# PRG_1_0.net
KiCad netlist of a schematic drawn in EAGLE
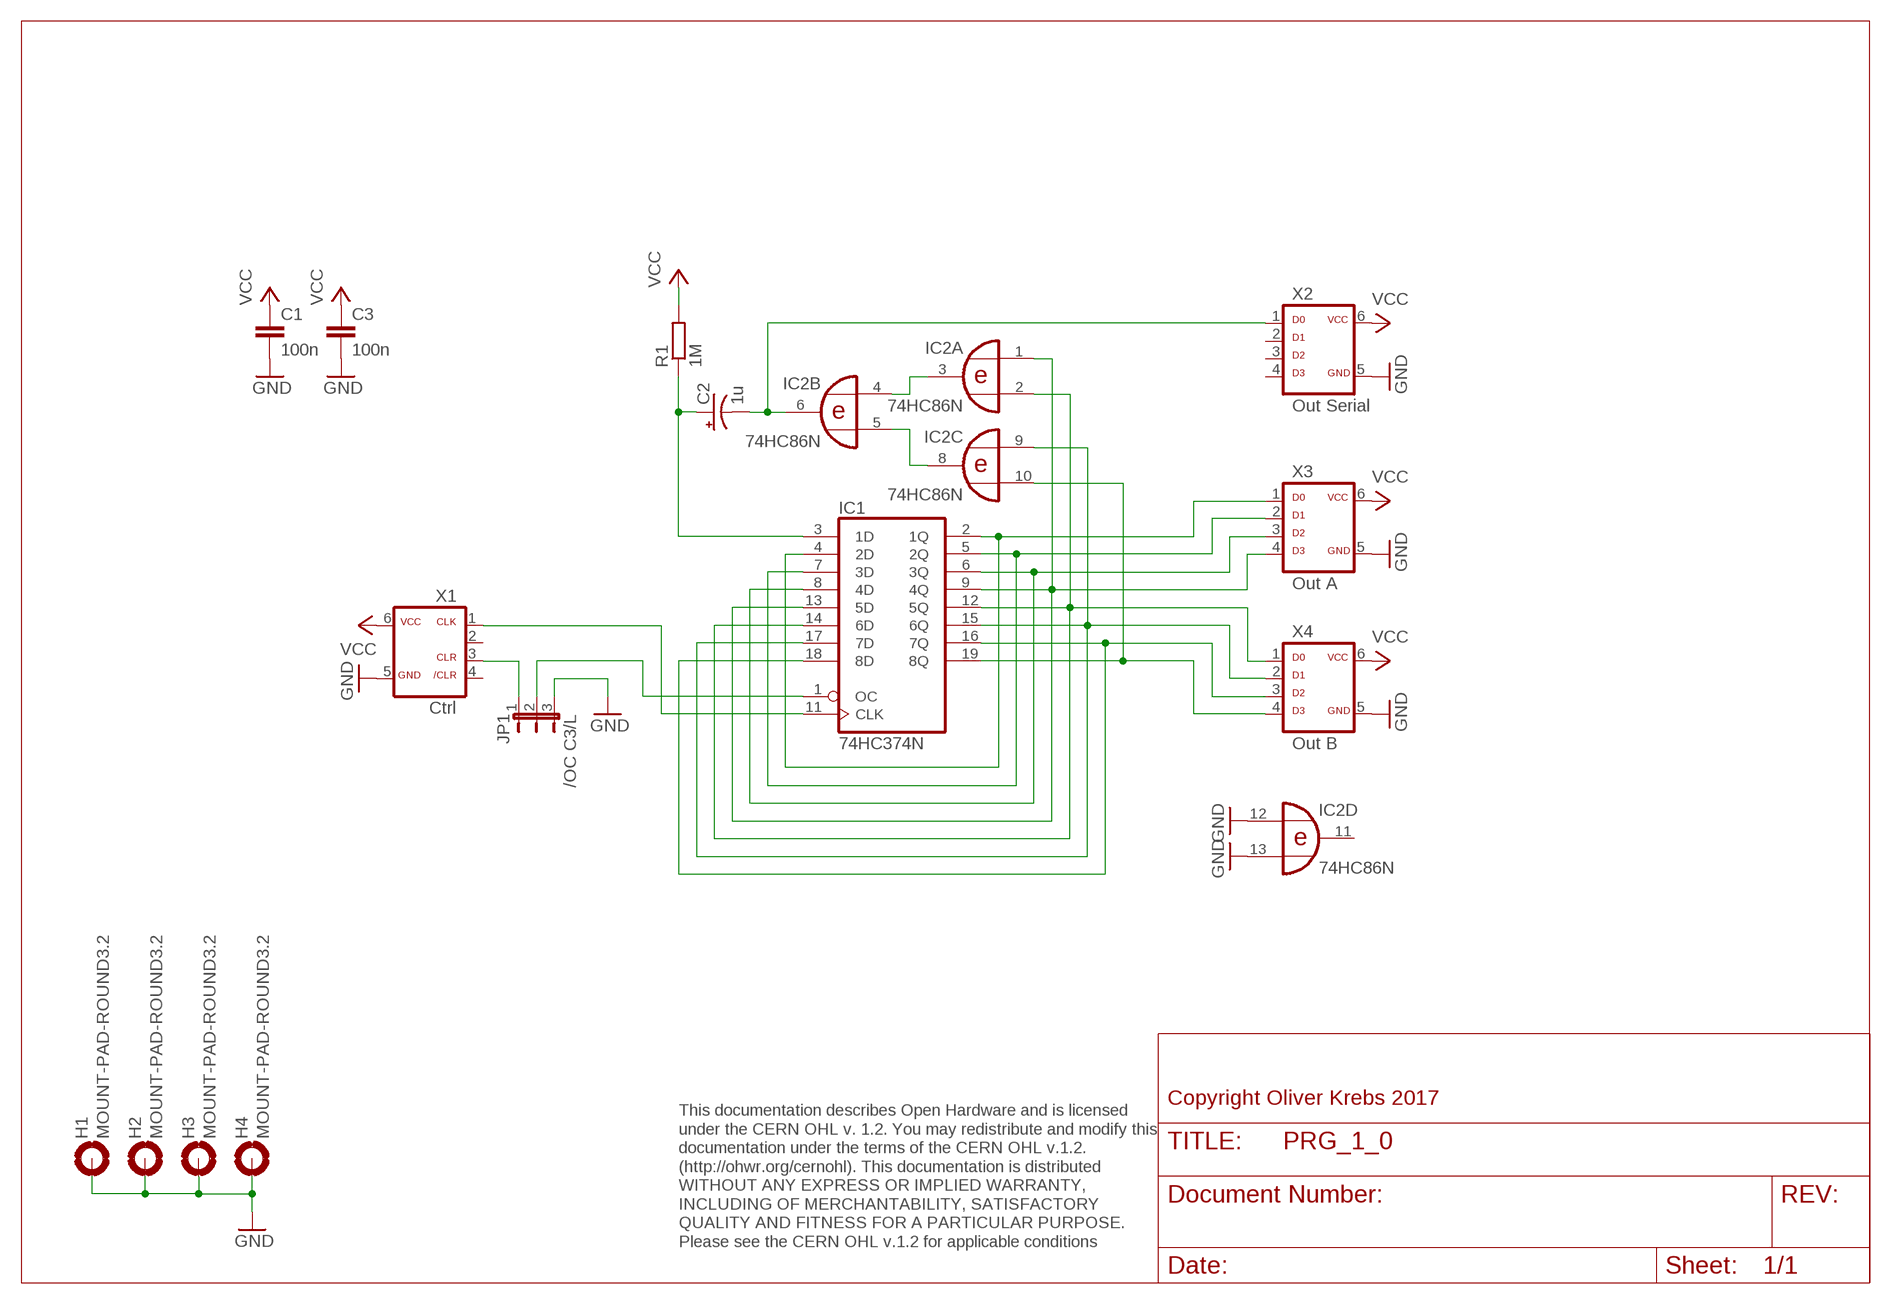
[diagram p0: schematic, sheet 1]

(export (version "E")
  (design (tool "Eeschema 10.0.6"))
  (components
    (comp (ref "C1")
      (value "100n")
      (footprint "eagle-import:C050-025X075")
      (libsource (lib "eagle-import") (part "C-EU050-025X075"))
    )
    (comp (ref "C2")
      (value "1u")
      (footprint "eagle-import:CPOL-RADIAL-10UF-25V")
      (libsource (lib "eagle-import") (part "CAP_POLPTH2"))
    )
    (comp (ref "C3")
      (value "100n")
      (footprint "eagle-import:C050-025X075")
      (libsource (lib "eagle-import") (part "C-EU050-025X075"))
    )
    (comp (ref "H1")
      (value "MOUNT-PAD-ROUND3.2")
      (footprint "eagle-import:3,2-PAD")
      (libsource (lib "eagle-import") (part "MOUNT-PAD-ROUND3.2"))
    )
    (comp (ref "H2")
      (value "MOUNT-PAD-ROUND3.2")
      (footprint "eagle-import:3,2-PAD")
      (libsource (lib "eagle-import") (part "MOUNT-PAD-ROUND3.2"))
    )
    (comp (ref "H3")
      (value "MOUNT-PAD-ROUND3.2")
      (footprint "eagle-import:3,2-PAD")
      (libsource (lib "eagle-import") (part "MOUNT-PAD-ROUND3.2"))
    )
    (comp (ref "H4")
      (value "MOUNT-PAD-ROUND3.2")
      (footprint "eagle-import:3,2-PAD")
      (libsource (lib "eagle-import") (part "MOUNT-PAD-ROUND3.2"))
    )
    (comp (ref "IC1")
      (value "74HC374N")
      (footprint "eagle-import:DIL20")
      (libsource (lib "eagle-import") (part "74374NHC"))
    )
    (comp (ref "IC2")
      (value "74HC86N")
      (footprint "eagle-import:DIL14")
      (libsource (lib "eagle-import") (part "7486NHC"))
    )
    (comp (ref "JP1")
      (value "/OC C3/L")
      (footprint "eagle-import:JP2-U")
      (libsource (lib "eagle-import") (part "JP2EJP2-U"))
    )
    (comp (ref "R1")
      (value "1M")
      (footprint "eagle-import:0207_10")
      (libsource (lib "eagle-import") (part "R-EU_0207/10"))
    )
    (comp (ref "X1")
      (value "Ctrl")
      (footprint "eagle-import:ML-6")
      (libsource (lib "eagle-import") (part "ML6C"))
    )
    (comp (ref "X2")
      (value "Out Serial")
      (footprint "eagle-import:ML-6")
      (libsource (lib "eagle-import") (part "ML6D"))
    )
    (comp (ref "X3")
      (value "Out A")
      (footprint "eagle-import:ML-6")
      (libsource (lib "eagle-import") (part "ML6D"))
    )
    (comp (ref "X4")
      (value "Out B")
      (footprint "eagle-import:ML-6")
      (libsource (lib "eagle-import") (part "ML6D"))
    )
  )
  (nets
    (net (code "1") (name "GND") (class "Default")
      (node (ref "C1") (pin "2") (pinfunction "2_2") (pintype "passive"))
      (node (ref "C3") (pin "2") (pinfunction "2_2") (pintype "passive"))
      (node (ref "H1") (pin "B3,2") (pinfunction "MOUNT_B3,2") (pintype "passive"))
      (node (ref "H2") (pin "B3,2") (pinfunction "MOUNT_B3,2") (pintype "passive"))
      (node (ref "H3") (pin "B3,2") (pinfunction "MOUNT_B3,2") (pintype "passive"))
      (node (ref "H4") (pin "B3,2") (pinfunction "MOUNT_B3,2") (pintype "passive"))
      (node (ref "IC2") (pin "12") (pinfunction "I0_12") (pintype "input"))
      (node (ref "IC2") (pin "13") (pinfunction "I1_13") (pintype "input"))
      (node (ref "JP1") (pin "3") (pinfunction "3_3") (pintype "passive"))
      (node (ref "X1") (pin "5") (pinfunction "5_5") (pintype "passive"))
      (node (ref "X2") (pin "5") (pinfunction "5_5") (pintype "passive"))
      (node (ref "X3") (pin "5") (pinfunction "5_5") (pintype "passive"))
      (node (ref "X4") (pin "5") (pinfunction "5_5") (pintype "passive"))
    )
    (net (code "2") (name "Net-(C2-+)") (class "Default")
      (node (ref "C2") (pin "1") (pinfunction "+_1") (pintype "passive"))
      (node (ref "IC1") (pin "3") (pinfunction "1D_3") (pintype "input"))
      (node (ref "R1") (pin "1") (pinfunction "1_1") (pintype "passive"))
    )
    (net (code "3") (name "Net-(C2--)") (class "Default")
      (node (ref "C2") (pin "2") (pinfunction "-_2") (pintype "passive"))
      (node (ref "IC2") (pin "6") (pinfunction "O_6") (pintype "output"))
      (node (ref "X2") (pin "1") (pinfunction "1_1") (pintype "passive"))
    )
    (net (code "4") (name "Net-(IC1A-1Q)") (class "Default")
      (node (ref "IC1") (pin "2") (pinfunction "1Q_2") (pintype "tri_state"))
      (node (ref "IC1") (pin "4") (pinfunction "2D_4") (pintype "input"))
      (node (ref "X3") (pin "1") (pinfunction "1_1") (pintype "passive"))
    )
    (net (code "5") (name "Net-(IC1A-2Q)") (class "Default")
      (node (ref "IC1") (pin "5") (pinfunction "2Q_5") (pintype "tri_state"))
      (node (ref "IC1") (pin "7") (pinfunction "3D_7") (pintype "input"))
      (node (ref "X3") (pin "2") (pinfunction "2_2") (pintype "passive"))
    )
    (net (code "6") (name "Net-(IC1A-3Q)") (class "Default")
      (node (ref "IC1") (pin "6") (pinfunction "3Q_6") (pintype "tri_state"))
      (node (ref "IC1") (pin "8") (pinfunction "4D_8") (pintype "input"))
      (node (ref "X3") (pin "3") (pinfunction "3_3") (pintype "passive"))
    )
    (net (code "7") (name "Net-(IC1A-4Q)") (class "Default")
      (node (ref "IC1") (pin "13") (pinfunction "5D_13") (pintype "input"))
      (node (ref "IC1") (pin "9") (pinfunction "4Q_9") (pintype "tri_state"))
      (node (ref "IC2") (pin "1") (pinfunction "I0_1") (pintype "input"))
      (node (ref "X3") (pin "4") (pinfunction "4_4") (pintype "passive"))
    )
    (net (code "8") (name "Net-(IC1A-5Q)") (class "Default")
      (node (ref "IC1") (pin "12") (pinfunction "5Q_12") (pintype "tri_state"))
      (node (ref "IC1") (pin "14") (pinfunction "6D_14") (pintype "input"))
      (node (ref "IC2") (pin "2") (pinfunction "I1_2") (pintype "input"))
      (node (ref "X4") (pin "1") (pinfunction "1_1") (pintype "passive"))
    )
    (net (code "9") (name "Net-(IC1A-6Q)") (class "Default")
      (node (ref "IC1") (pin "15") (pinfunction "6Q_15") (pintype "tri_state"))
      (node (ref "IC1") (pin "17") (pinfunction "7D_17") (pintype "input"))
      (node (ref "IC2") (pin "9") (pinfunction "I0_9") (pintype "input"))
      (node (ref "X4") (pin "2") (pinfunction "2_2") (pintype "passive"))
    )
    (net (code "10") (name "Net-(IC1A-7Q)") (class "Default")
      (node (ref "IC1") (pin "16") (pinfunction "7Q_16") (pintype "tri_state"))
      (node (ref "IC1") (pin "18") (pinfunction "8D_18") (pintype "input"))
      (node (ref "X4") (pin "3") (pinfunction "3_3") (pintype "passive"))
    )
    (net (code "11") (name "Net-(IC1A-8Q)") (class "Default")
      (node (ref "IC1") (pin "19") (pinfunction "8Q_19") (pintype "tri_state"))
      (node (ref "IC2") (pin "10") (pinfunction "I1_10") (pintype "input"))
      (node (ref "X4") (pin "4") (pinfunction "4_4") (pintype "passive"))
    )
    (net (code "12") (name "Net-(IC1A-CLK)") (class "Default")
      (node (ref "IC1") (pin "11") (pinfunction "CLK_11") (pintype "input"))
      (node (ref "X1") (pin "1") (pinfunction "1_1") (pintype "passive"))
    )
    (net (code "13") (name "Net-(IC1A-OC)") (class "Default")
      (node (ref "IC1") (pin "1") (pinfunction "OC_1") (pintype "input"))
      (node (ref "JP1") (pin "2") (pinfunction "2_2") (pintype "passive"))
    )
    (net (code "14") (name "Net-(IC2A-O)") (class "Default")
      (node (ref "IC2") (pin "3") (pinfunction "O_3") (pintype "output"))
      (node (ref "IC2") (pin "4") (pinfunction "I0_4") (pintype "input"))
    )
    (net (code "15") (name "Net-(IC2B-I1)") (class "Default")
      (node (ref "IC2") (pin "5") (pinfunction "I1_5") (pintype "input"))
      (node (ref "IC2") (pin "8") (pinfunction "O_8") (pintype "output"))
    )
    (net (code "16") (name "Net-(JP1-Pad1)") (class "Default")
      (node (ref "JP1") (pin "1") (pinfunction "1_1") (pintype "passive"))
      (node (ref "X1") (pin "3") (pinfunction "3_3") (pintype "passive"))
    )
    (net (code "17") (name "VCC") (class "Default")
      (node (ref "C1") (pin "1") (pinfunction "1_1") (pintype "passive"))
      (node (ref "C3") (pin "1") (pinfunction "1_1") (pintype "passive"))
      (node (ref "R1") (pin "2") (pinfunction "2_2") (pintype "passive"))
      (node (ref "X1") (pin "6") (pinfunction "6_6") (pintype "passive"))
      (node (ref "X2") (pin "6") (pinfunction "6_6") (pintype "passive"))
      (node (ref "X3") (pin "6") (pinfunction "6_6") (pintype "passive"))
      (node (ref "X4") (pin "6") (pinfunction "6_6") (pintype "passive"))
    )
    (net (code "18") (name "unconnected-(IC2D-O-Pad11)") (class "Default")
      (node (ref "IC2") (pin "11") (pinfunction "O_11") (pintype "output"))
    )
    (net (code "19") (name "unconnected-(X1-Pad2)") (class "Default")
      (node (ref "X1") (pin "2") (pinfunction "2_2") (pintype "passive"))
    )
    (net (code "20") (name "unconnected-(X1-Pad4)") (class "Default")
      (node (ref "X1") (pin "4") (pinfunction "4_4") (pintype "passive"))
    )
    (net (code "21") (name "unconnected-(X2-Pad2)") (class "Default")
      (node (ref "X2") (pin "2") (pinfunction "2_2") (pintype "passive"))
    )
    (net (code "22") (name "unconnected-(X2-Pad3)") (class "Default")
      (node (ref "X2") (pin "3") (pinfunction "3_3") (pintype "passive"))
    )
    (net (code "23") (name "unconnected-(X2-Pad4)") (class "Default")
      (node (ref "X2") (pin "4") (pinfunction "4_4") (pintype "passive"))
    )
  )
)
